# loom_motordriver.net
KiCad netlist of a schematic drawn in EAGLE
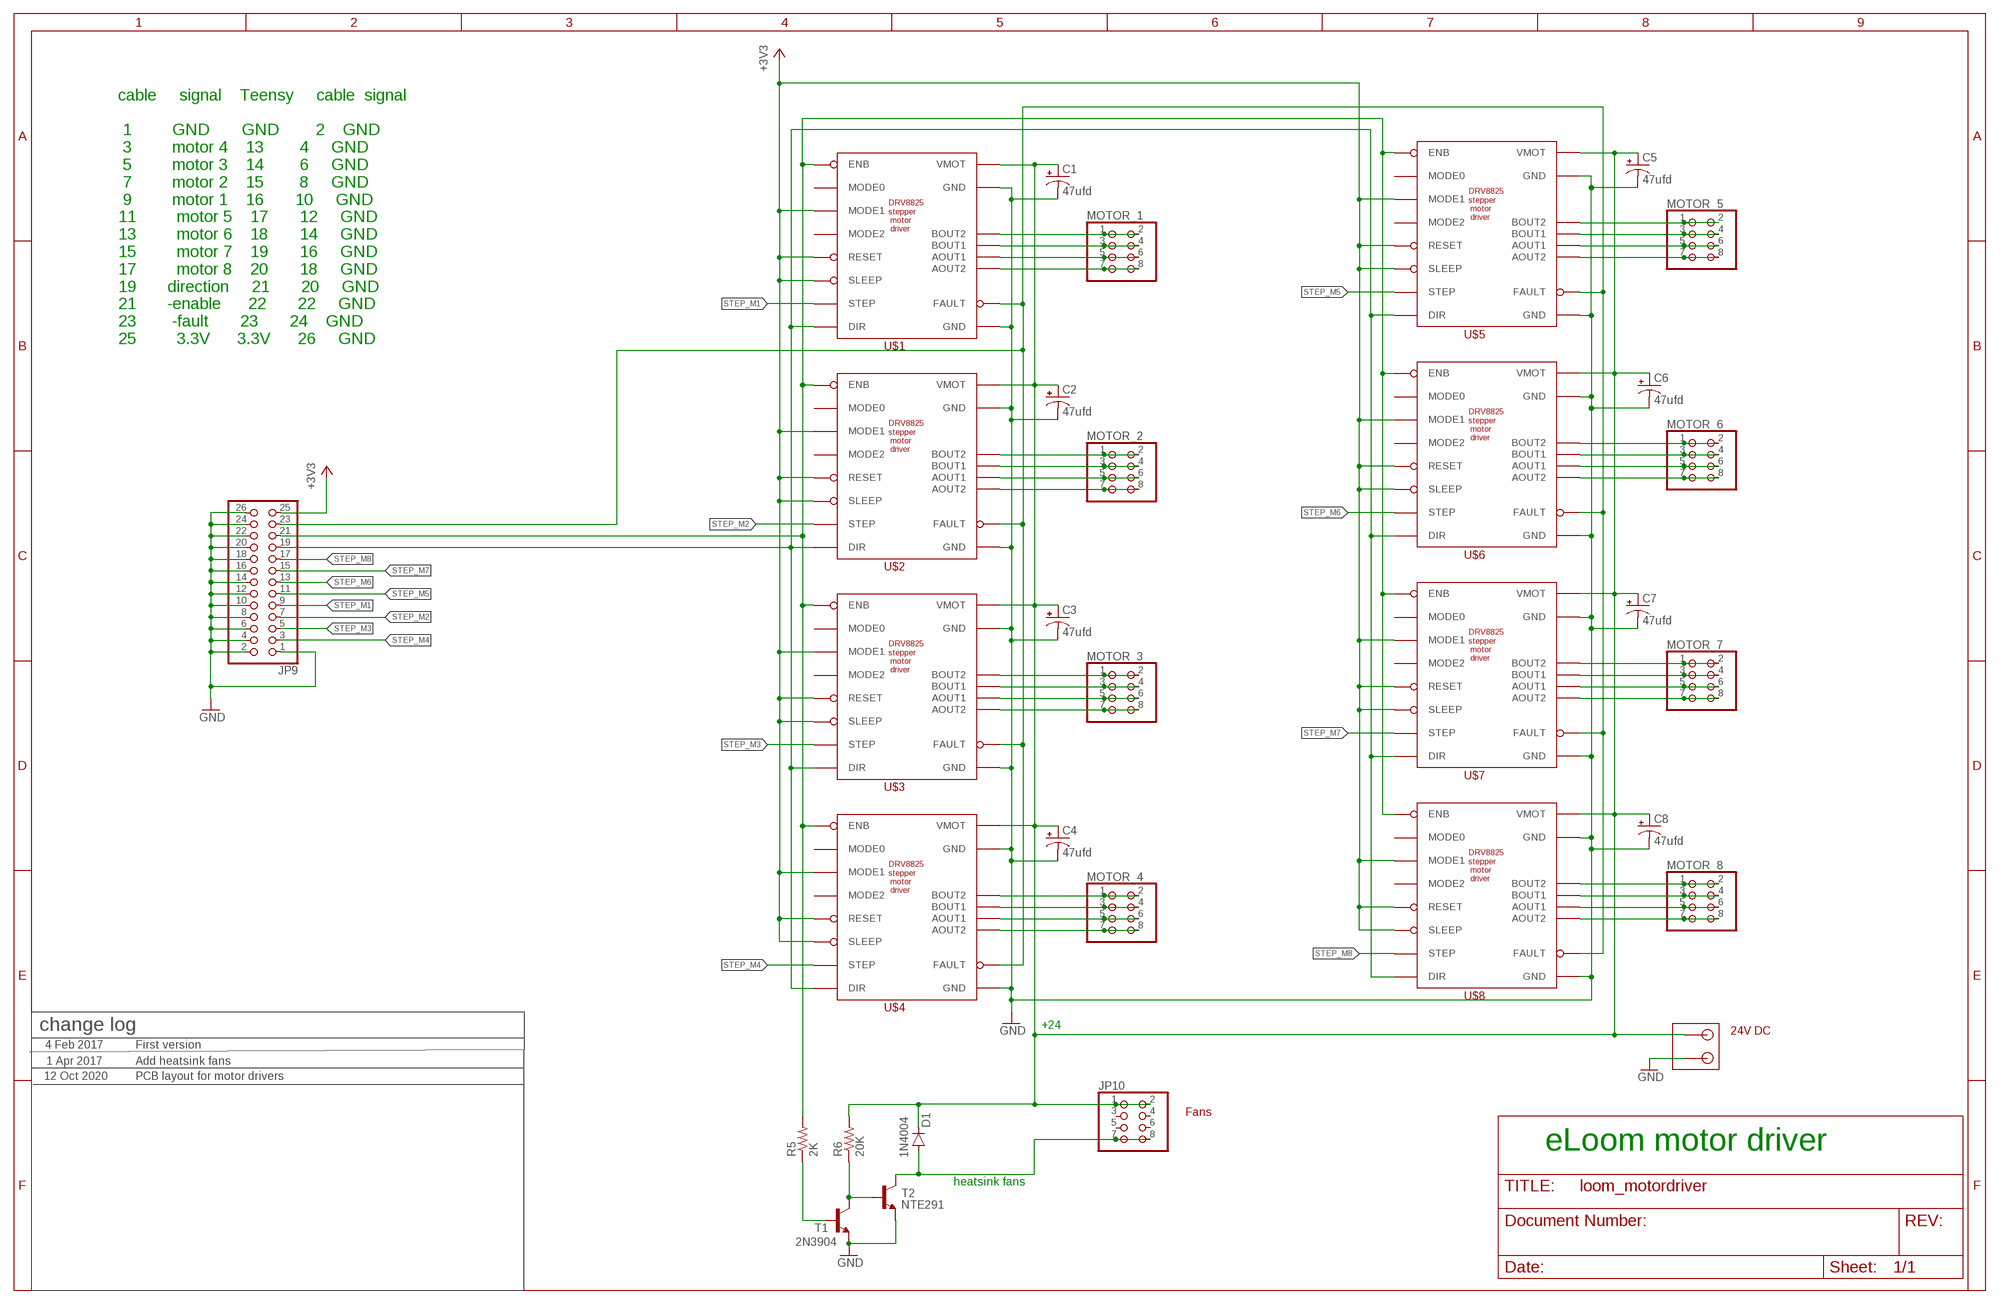
[diagram p0: schematic, sheet 1]

(export (version "E")
  (design (tool "Eeschema 10.0.6"))
  (components
    (comp (ref "C1")
      (value "47ufd")
      (footprint "eagle-import:E2,5-6")
      (libsource (lib "eagle-import") (part "CPOL-USE2.5-6"))
    )
    (comp (ref "C2")
      (value "47ufd")
      (footprint "eagle-import:E2,5-6")
      (libsource (lib "eagle-import") (part "CPOL-USE2.5-6"))
    )
    (comp (ref "C3")
      (value "47ufd")
      (footprint "eagle-import:E2,5-6")
      (libsource (lib "eagle-import") (part "CPOL-USE2.5-6"))
    )
    (comp (ref "C4")
      (value "47ufd")
      (footprint "eagle-import:E2,5-6")
      (libsource (lib "eagle-import") (part "CPOL-USE2.5-6"))
    )
    (comp (ref "C5")
      (value "47ufd")
      (footprint "eagle-import:E2,5-6")
      (libsource (lib "eagle-import") (part "CPOL-USE2.5-6"))
    )
    (comp (ref "C6")
      (value "47ufd")
      (footprint "eagle-import:E2,5-6")
      (libsource (lib "eagle-import") (part "CPOL-USE2.5-6"))
    )
    (comp (ref "C7")
      (value "47ufd")
      (footprint "eagle-import:E2,5-6")
      (libsource (lib "eagle-import") (part "CPOL-USE2.5-6"))
    )
    (comp (ref "C8")
      (value "47ufd")
      (footprint "eagle-import:E2,5-6")
      (libsource (lib "eagle-import") (part "CPOL-USE2.5-6"))
    )
    (comp (ref "D1")
      (value "1N4004")
      (footprint "eagle-import:DO41-10")
      (libsource (lib "eagle-import") (part "1N4004"))
    )
    (comp (ref "JP9")
      (value "PINHD-2X13")
      (footprint "eagle-import:2X13")
      (libsource (lib "eagle-import") (part "PINHD-2X13"))
    )
    (comp (ref "JP10")
      (value "PINHD-2X4")
      (footprint "eagle-import:2X04")
      (libsource (lib "eagle-import") (part "pinhead_325_PINHD-2X4"))
    )
    (comp (ref "MOTOR_1")
      (value "PINHD-2X4")
      (footprint "eagle-import:2X04")
      (libsource (lib "eagle-import") (part "PINHD-2X4"))
    )
    (comp (ref "MOTOR_2")
      (value "PINHD-2X4")
      (footprint "eagle-import:2X04")
      (libsource (lib "eagle-import") (part "PINHD-2X4"))
    )
    (comp (ref "MOTOR_3")
      (value "PINHD-2X4")
      (footprint "eagle-import:2X04")
      (libsource (lib "eagle-import") (part "PINHD-2X4"))
    )
    (comp (ref "MOTOR_4")
      (value "PINHD-2X4")
      (footprint "eagle-import:2X04")
      (libsource (lib "eagle-import") (part "PINHD-2X4"))
    )
    (comp (ref "MOTOR_5")
      (value "PINHD-2X4")
      (footprint "eagle-import:2X04")
      (libsource (lib "eagle-import") (part "PINHD-2X4"))
    )
    (comp (ref "MOTOR_6")
      (value "PINHD-2X4")
      (footprint "eagle-import:2X04")
      (libsource (lib "eagle-import") (part "PINHD-2X4"))
    )
    (comp (ref "MOTOR_7")
      (value "PINHD-2X4")
      (footprint "eagle-import:2X04")
      (libsource (lib "eagle-import") (part "PINHD-2X4"))
    )
    (comp (ref "MOTOR_8")
      (value "PINHD-2X4")
      (footprint "eagle-import:2X04")
      (libsource (lib "eagle-import") (part "PINHD-2X4"))
    )
    (comp (ref "R5")
      (value "2K")
      (footprint "eagle-import:0204_7")
      (libsource (lib "eagle-import") (part "R-US_0204/7"))
    )
    (comp (ref "R6")
      (value "20K")
      (footprint "eagle-import:0204_7")
      (libsource (lib "eagle-import") (part "R-US_0204/7"))
    )
    (comp (ref "T1")
      (value "2N3904")
      (footprint "eagle-import:TO92")
      (libsource (lib "eagle-import") (part "2N3904"))
    )
    (comp (ref "T2")
      (value "NTE291")
      (footprint "eagle-import:TO220")
      (libsource (lib "eagle-import") (part "-NPN-TO220"))
    )
    (comp (ref "U$1")
      (value "DRV8825_STEPPER_MOTOR_DRIVER")
      (footprint "eagle-import:DRV8825_STEPPER_MOTOR_DRIVER")
      (libsource (lib "eagle-import") (part "DRV8825_STEPPER_MOTOR_DRIVER"))
    )
    (comp (ref "U$2")
      (value "DRV8825_STEPPER_MOTOR_DRIVER")
      (footprint "eagle-import:DRV8825_STEPPER_MOTOR_DRIVER")
      (libsource (lib "eagle-import") (part "DRV8825_STEPPER_MOTOR_DRIVER"))
    )
    (comp (ref "U$3")
      (value "DRV8825_STEPPER_MOTOR_DRIVER")
      (footprint "eagle-import:DRV8825_STEPPER_MOTOR_DRIVER")
      (libsource (lib "eagle-import") (part "DRV8825_STEPPER_MOTOR_DRIVER"))
    )
    (comp (ref "U$4")
      (value "DRV8825_STEPPER_MOTOR_DRIVER")
      (footprint "eagle-import:DRV8825_STEPPER_MOTOR_DRIVER")
      (libsource (lib "eagle-import") (part "DRV8825_STEPPER_MOTOR_DRIVER"))
    )
    (comp (ref "U$5")
      (value "DRV8825_STEPPER_MOTOR_DRIVER")
      (footprint "eagle-import:DRV8825_STEPPER_MOTOR_DRIVER")
      (libsource (lib "eagle-import") (part "DRV8825_STEPPER_MOTOR_DRIVER"))
    )
    (comp (ref "U$6")
      (value "DRV8825_STEPPER_MOTOR_DRIVER")
      (footprint "eagle-import:DRV8825_STEPPER_MOTOR_DRIVER")
      (libsource (lib "eagle-import") (part "DRV8825_STEPPER_MOTOR_DRIVER"))
    )
    (comp (ref "U$7")
      (value "DRV8825_STEPPER_MOTOR_DRIVER")
      (footprint "eagle-import:DRV8825_STEPPER_MOTOR_DRIVER")
      (libsource (lib "eagle-import") (part "DRV8825_STEPPER_MOTOR_DRIVER"))
    )
    (comp (ref "U$8")
      (value "DRV8825_STEPPER_MOTOR_DRIVER")
      (footprint "eagle-import:DRV8825_STEPPER_MOTOR_DRIVER")
      (libsource (lib "eagle-import") (part "DRV8825_STEPPER_MOTOR_DRIVER"))
    )
    (comp (ref "U$9")
      (value "CONNECTOR-2PIN")
      (footprint "eagle-import:CONNECTOR-2PIN-5MM")
      (libsource (lib "eagle-import") (part "CONNECTOR-2PIN"))
    )
  )
  (nets
    (net (code "1") (name "+3V3") (class "Default")
      (node (ref "JP9") (pin "25") (pinfunction "25_25") (pintype "passive"))
      (node (ref "U$1") (pin "P$3") (pinfunction "MODE1_P$3") (pintype "input"))
      (node (ref "U$1") (pin "P$5") (pinfunction "RESET_P$5") (pintype "input"))
      (node (ref "U$1") (pin "P$6") (pinfunction "SLEEP_P$6") (pintype "input"))
      (node (ref "U$2") (pin "P$3") (pinfunction "MODE1_P$3") (pintype "input"))
      (node (ref "U$2") (pin "P$5") (pinfunction "RESET_P$5") (pintype "input"))
      (node (ref "U$2") (pin "P$6") (pinfunction "SLEEP_P$6") (pintype "input"))
      (node (ref "U$3") (pin "P$3") (pinfunction "MODE1_P$3") (pintype "input"))
      (node (ref "U$3") (pin "P$5") (pinfunction "RESET_P$5") (pintype "input"))
      (node (ref "U$3") (pin "P$6") (pinfunction "SLEEP_P$6") (pintype "input"))
      (node (ref "U$4") (pin "P$3") (pinfunction "MODE1_P$3") (pintype "input"))
      (node (ref "U$4") (pin "P$5") (pinfunction "RESET_P$5") (pintype "input"))
      (node (ref "U$4") (pin "P$6") (pinfunction "SLEEP_P$6") (pintype "input"))
      (node (ref "U$5") (pin "P$3") (pinfunction "MODE1_P$3") (pintype "input"))
      (node (ref "U$5") (pin "P$5") (pinfunction "RESET_P$5") (pintype "input"))
      (node (ref "U$5") (pin "P$6") (pinfunction "SLEEP_P$6") (pintype "input"))
      (node (ref "U$6") (pin "P$3") (pinfunction "MODE1_P$3") (pintype "input"))
      (node (ref "U$6") (pin "P$5") (pinfunction "RESET_P$5") (pintype "input"))
      (node (ref "U$6") (pin "P$6") (pinfunction "SLEEP_P$6") (pintype "input"))
      (node (ref "U$7") (pin "P$3") (pinfunction "MODE1_P$3") (pintype "input"))
      (node (ref "U$7") (pin "P$5") (pinfunction "RESET_P$5") (pintype "input"))
      (node (ref "U$7") (pin "P$6") (pinfunction "SLEEP_P$6") (pintype "input"))
      (node (ref "U$8") (pin "P$3") (pinfunction "MODE1_P$3") (pintype "input"))
      (node (ref "U$8") (pin "P$5") (pinfunction "RESET_P$5") (pintype "input"))
      (node (ref "U$8") (pin "P$6") (pinfunction "SLEEP_P$6") (pintype "input"))
    )
    (net (code "2") (name "GND") (class "Default")
      (node (ref "C1") (pin "-") (pinfunction "-_-") (pintype "passive"))
      (node (ref "C2") (pin "-") (pinfunction "-_-") (pintype "passive"))
      (node (ref "C3") (pin "-") (pinfunction "-_-") (pintype "passive"))
      (node (ref "C4") (pin "-") (pinfunction "-_-") (pintype "passive"))
      (node (ref "C5") (pin "-") (pinfunction "-_-") (pintype "passive"))
      (node (ref "C6") (pin "-") (pinfunction "-_-") (pintype "passive"))
      (node (ref "C7") (pin "-") (pinfunction "-_-") (pintype "passive"))
      (node (ref "C8") (pin "-") (pinfunction "-_-") (pintype "passive"))
      (node (ref "JP9") (pin "1") (pinfunction "1_1") (pintype "passive"))
      (node (ref "JP9") (pin "10") (pinfunction "10_10") (pintype "passive"))
      (node (ref "JP9") (pin "12") (pinfunction "12_12") (pintype "passive"))
      (node (ref "JP9") (pin "14") (pinfunction "14_14") (pintype "passive"))
      (node (ref "JP9") (pin "16") (pinfunction "16_16") (pintype "passive"))
      (node (ref "JP9") (pin "18") (pinfunction "18_18") (pintype "passive"))
      (node (ref "JP9") (pin "2") (pinfunction "2_2") (pintype "passive"))
      (node (ref "JP9") (pin "20") (pinfunction "20_20") (pintype "passive"))
      (node (ref "JP9") (pin "22") (pinfunction "22_22") (pintype "passive"))
      (node (ref "JP9") (pin "24") (pinfunction "24_24") (pintype "passive"))
      (node (ref "JP9") (pin "26") (pinfunction "26_26") (pintype "passive"))
      (node (ref "JP9") (pin "4") (pinfunction "4_4") (pintype "passive"))
      (node (ref "JP9") (pin "6") (pinfunction "6_6") (pintype "passive"))
      (node (ref "JP9") (pin "8") (pinfunction "8_8") (pintype "passive"))
      (node (ref "T1") (pin "3") (pinfunction "E_3") (pintype "passive"))
      (node (ref "T2") (pin "3") (pinfunction "E_3") (pintype "passive"))
      (node (ref "U$1") (pin "P$15") (pinfunction "GND_P$15") (pintype "power_in"))
      (node (ref "U$1") (pin "P$9") (pinfunction "GND_P$9") (pintype "power_in"))
      (node (ref "U$2") (pin "P$15") (pinfunction "GND_P$15") (pintype "power_in"))
      (node (ref "U$2") (pin "P$9") (pinfunction "GND_P$9") (pintype "power_in"))
      (node (ref "U$3") (pin "P$15") (pinfunction "GND_P$15") (pintype "power_in"))
      (node (ref "U$3") (pin "P$9") (pinfunction "GND_P$9") (pintype "power_in"))
      (node (ref "U$4") (pin "P$15") (pinfunction "GND_P$15") (pintype "power_in"))
      (node (ref "U$4") (pin "P$9") (pinfunction "GND_P$9") (pintype "power_in"))
      (node (ref "U$5") (pin "P$15") (pinfunction "GND_P$15") (pintype "power_in"))
      (node (ref "U$5") (pin "P$9") (pinfunction "GND_P$9") (pintype "power_in"))
      (node (ref "U$6") (pin "P$15") (pinfunction "GND_P$15") (pintype "power_in"))
      (node (ref "U$6") (pin "P$9") (pinfunction "GND_P$9") (pintype "power_in"))
      (node (ref "U$7") (pin "P$15") (pinfunction "GND_P$15") (pintype "power_in"))
      (node (ref "U$7") (pin "P$9") (pinfunction "GND_P$9") (pintype "power_in"))
      (node (ref "U$8") (pin "P$15") (pinfunction "GND_P$15") (pintype "power_in"))
      (node (ref "U$8") (pin "P$9") (pinfunction "GND_P$9") (pintype "power_in"))
      (node (ref "U$9") (pin "P$2") (pinfunction "P$2_P$2") (pintype "bidirectional"))
    )
    (net (code "3") (name "Net-(T1-B)") (class "Default")
      (node (ref "R5") (pin "1") (pinfunction "1_1") (pintype "passive"))
      (node (ref "T1") (pin "2") (pinfunction "B_2") (pintype "passive"))
    )
    (net (code "4") (name "Net-(T1-C)") (class "Default")
      (node (ref "R6") (pin "1") (pinfunction "1_1") (pintype "passive"))
      (node (ref "T1") (pin "1") (pinfunction "C_1") (pintype "passive"))
      (node (ref "T2") (pin "1") (pinfunction "B_1") (pintype "passive"))
    )
    (net (code "5") (name "Net-(T2-C)") (class "Default")
      (node (ref "D1") (pin "A") (pinfunction "A_A") (pintype "passive"))
      (node (ref "JP10") (pin "7") (pinfunction "7_7") (pintype "passive"))
      (node (ref "JP10") (pin "8") (pinfunction "8_8") (pintype "passive"))
      (node (ref "T2") (pin "2") (pinfunction "C_2") (pintype "passive"))
    )
    (net (code "6") (name "Net-(U$1-AOUT1)") (class "Default")
      (node (ref "MOTOR_1") (pin "5") (pinfunction "5_5") (pintype "passive"))
      (node (ref "MOTOR_1") (pin "6") (pinfunction "6_6") (pintype "passive"))
      (node (ref "U$1") (pin "P$12") (pinfunction "AOUT1_P$12") (pintype "passive"))
    )
    (net (code "7") (name "Net-(U$1-AOUT2)") (class "Default")
      (node (ref "MOTOR_1") (pin "7") (pinfunction "7_7") (pintype "passive"))
      (node (ref "MOTOR_1") (pin "8") (pinfunction "8_8") (pintype "passive"))
      (node (ref "U$1") (pin "P$11") (pinfunction "AOUT2_P$11") (pintype "passive"))
    )
    (net (code "8") (name "Net-(U$1-BOUT1)") (class "Default")
      (node (ref "MOTOR_1") (pin "3") (pinfunction "3_3") (pintype "passive"))
      (node (ref "MOTOR_1") (pin "4") (pinfunction "4_4") (pintype "passive"))
      (node (ref "U$1") (pin "P$13") (pinfunction "BOUT1_P$13") (pintype "passive"))
    )
    (net (code "9") (name "Net-(U$1-BOUT2)") (class "Default")
      (node (ref "MOTOR_1") (pin "1") (pinfunction "1_1") (pintype "passive"))
      (node (ref "MOTOR_1") (pin "2") (pinfunction "2_2") (pintype "passive"))
      (node (ref "U$1") (pin "P$14") (pinfunction "BOUT2_P$14") (pintype "passive"))
    )
    (net (code "10") (name "Net-(U$1-DIR)") (class "Default")
      (node (ref "JP9") (pin "19") (pinfunction "19_19") (pintype "passive"))
      (node (ref "U$1") (pin "P$8") (pinfunction "DIR_P$8") (pintype "input"))
      (node (ref "U$2") (pin "P$8") (pinfunction "DIR_P$8") (pintype "input"))
      (node (ref "U$3") (pin "P$8") (pinfunction "DIR_P$8") (pintype "input"))
      (node (ref "U$4") (pin "P$8") (pinfunction "DIR_P$8") (pintype "input"))
      (node (ref "U$5") (pin "P$8") (pinfunction "DIR_P$8") (pintype "input"))
      (node (ref "U$6") (pin "P$8") (pinfunction "DIR_P$8") (pintype "input"))
      (node (ref "U$7") (pin "P$8") (pinfunction "DIR_P$8") (pintype "input"))
      (node (ref "U$8") (pin "P$8") (pinfunction "DIR_P$8") (pintype "input"))
    )
    (net (code "11") (name "Net-(U$1-ENB)") (class "Default")
      (node (ref "JP9") (pin "21") (pinfunction "21_21") (pintype "passive"))
      (node (ref "R5") (pin "2") (pinfunction "2_2") (pintype "passive"))
      (node (ref "U$1") (pin "P$1") (pinfunction "ENB_P$1") (pintype "input"))
      (node (ref "U$2") (pin "P$1") (pinfunction "ENB_P$1") (pintype "input"))
      (node (ref "U$3") (pin "P$1") (pinfunction "ENB_P$1") (pintype "input"))
      (node (ref "U$4") (pin "P$1") (pinfunction "ENB_P$1") (pintype "input"))
      (node (ref "U$5") (pin "P$1") (pinfunction "ENB_P$1") (pintype "input"))
      (node (ref "U$6") (pin "P$1") (pinfunction "ENB_P$1") (pintype "input"))
      (node (ref "U$7") (pin "P$1") (pinfunction "ENB_P$1") (pintype "input"))
      (node (ref "U$8") (pin "P$1") (pinfunction "ENB_P$1") (pintype "input"))
    )
    (net (code "12") (name "Net-(U$1-FAULT)") (class "Default")
      (node (ref "JP9") (pin "23") (pinfunction "23_23") (pintype "passive"))
      (node (ref "U$1") (pin "P$10") (pinfunction "FAULT_P$10") (pintype "output"))
      (node (ref "U$2") (pin "P$10") (pinfunction "FAULT_P$10") (pintype "output"))
      (node (ref "U$3") (pin "P$10") (pinfunction "FAULT_P$10") (pintype "output"))
      (node (ref "U$4") (pin "P$10") (pinfunction "FAULT_P$10") (pintype "output"))
      (node (ref "U$5") (pin "P$10") (pinfunction "FAULT_P$10") (pintype "output"))
      (node (ref "U$6") (pin "P$10") (pinfunction "FAULT_P$10") (pintype "output"))
      (node (ref "U$7") (pin "P$10") (pinfunction "FAULT_P$10") (pintype "output"))
      (node (ref "U$8") (pin "P$10") (pinfunction "FAULT_P$10") (pintype "output"))
    )
    (net (code "13") (name "Net-(U$1-VMOT)") (class "Default")
      (node (ref "C1") (pin "+") (pinfunction "+_+") (pintype "passive"))
      (node (ref "C2") (pin "+") (pinfunction "+_+") (pintype "passive"))
      (node (ref "C3") (pin "+") (pinfunction "+_+") (pintype "passive"))
      (node (ref "C4") (pin "+") (pinfunction "+_+") (pintype "passive"))
      (node (ref "C5") (pin "+") (pinfunction "+_+") (pintype "passive"))
      (node (ref "C6") (pin "+") (pinfunction "+_+") (pintype "passive"))
      (node (ref "C7") (pin "+") (pinfunction "+_+") (pintype "passive"))
      (node (ref "C8") (pin "+") (pinfunction "+_+") (pintype "passive"))
      (node (ref "D1") (pin "C") (pinfunction "C_C") (pintype "passive"))
      (node (ref "JP10") (pin "1") (pinfunction "1_1") (pintype "passive"))
      (node (ref "JP10") (pin "2") (pinfunction "2_2") (pintype "passive"))
      (node (ref "R6") (pin "2") (pinfunction "2_2") (pintype "passive"))
      (node (ref "U$1") (pin "P$16") (pinfunction "VMOT_P$16") (pintype "power_in"))
      (node (ref "U$2") (pin "P$16") (pinfunction "VMOT_P$16") (pintype "power_in"))
      (node (ref "U$3") (pin "P$16") (pinfunction "VMOT_P$16") (pintype "power_in"))
      (node (ref "U$4") (pin "P$16") (pinfunction "VMOT_P$16") (pintype "power_in"))
      (node (ref "U$5") (pin "P$16") (pinfunction "VMOT_P$16") (pintype "power_in"))
      (node (ref "U$6") (pin "P$16") (pinfunction "VMOT_P$16") (pintype "power_in"))
      (node (ref "U$7") (pin "P$16") (pinfunction "VMOT_P$16") (pintype "power_in"))
      (node (ref "U$8") (pin "P$16") (pinfunction "VMOT_P$16") (pintype "power_in"))
      (node (ref "U$9") (pin "P$1") (pinfunction "P$1_P$1") (pintype "bidirectional"))
    )
    (net (code "14") (name "Net-(U$2-AOUT1)") (class "Default")
      (node (ref "MOTOR_2") (pin "5") (pinfunction "5_5") (pintype "passive"))
      (node (ref "MOTOR_2") (pin "6") (pinfunction "6_6") (pintype "passive"))
      (node (ref "U$2") (pin "P$12") (pinfunction "AOUT1_P$12") (pintype "passive"))
    )
    (net (code "15") (name "Net-(U$2-AOUT2)") (class "Default")
      (node (ref "MOTOR_2") (pin "7") (pinfunction "7_7") (pintype "passive"))
      (node (ref "MOTOR_2") (pin "8") (pinfunction "8_8") (pintype "passive"))
      (node (ref "U$2") (pin "P$11") (pinfunction "AOUT2_P$11") (pintype "passive"))
    )
    (net (code "16") (name "Net-(U$2-BOUT1)") (class "Default")
      (node (ref "MOTOR_2") (pin "3") (pinfunction "3_3") (pintype "passive"))
      (node (ref "MOTOR_2") (pin "4") (pinfunction "4_4") (pintype "passive"))
      (node (ref "U$2") (pin "P$13") (pinfunction "BOUT1_P$13") (pintype "passive"))
    )
    (net (code "17") (name "Net-(U$2-BOUT2)") (class "Default")
      (node (ref "MOTOR_2") (pin "1") (pinfunction "1_1") (pintype "passive"))
      (node (ref "MOTOR_2") (pin "2") (pinfunction "2_2") (pintype "passive"))
      (node (ref "U$2") (pin "P$14") (pinfunction "BOUT2_P$14") (pintype "passive"))
    )
    (net (code "18") (name "Net-(U$3-AOUT1)") (class "Default")
      (node (ref "MOTOR_3") (pin "5") (pinfunction "5_5") (pintype "passive"))
      (node (ref "MOTOR_3") (pin "6") (pinfunction "6_6") (pintype "passive"))
      (node (ref "U$3") (pin "P$12") (pinfunction "AOUT1_P$12") (pintype "passive"))
    )
    (net (code "19") (name "Net-(U$3-AOUT2)") (class "Default")
      (node (ref "MOTOR_3") (pin "7") (pinfunction "7_7") (pintype "passive"))
      (node (ref "MOTOR_3") (pin "8") (pinfunction "8_8") (pintype "passive"))
      (node (ref "U$3") (pin "P$11") (pinfunction "AOUT2_P$11") (pintype "passive"))
    )
    (net (code "20") (name "Net-(U$3-BOUT1)") (class "Default")
      (node (ref "MOTOR_3") (pin "3") (pinfunction "3_3") (pintype "passive"))
      (node (ref "MOTOR_3") (pin "4") (pinfunction "4_4") (pintype "passive"))
      (node (ref "U$3") (pin "P$13") (pinfunction "BOUT1_P$13") (pintype "passive"))
    )
    (net (code "21") (name "Net-(U$3-BOUT2)") (class "Default")
      (node (ref "MOTOR_3") (pin "1") (pinfunction "1_1") (pintype "passive"))
      (node (ref "MOTOR_3") (pin "2") (pinfunction "2_2") (pintype "passive"))
      (node (ref "U$3") (pin "P$14") (pinfunction "BOUT2_P$14") (pintype "passive"))
    )
    (net (code "22") (name "Net-(U$4-AOUT1)") (class "Default")
      (node (ref "MOTOR_4") (pin "5") (pinfunction "5_5") (pintype "passive"))
      (node (ref "MOTOR_4") (pin "6") (pinfunction "6_6") (pintype "passive"))
      (node (ref "U$4") (pin "P$12") (pinfunction "AOUT1_P$12") (pintype "passive"))
    )
    (net (code "23") (name "Net-(U$4-AOUT2)") (class "Default")
      (node (ref "MOTOR_4") (pin "7") (pinfunction "7_7") (pintype "passive"))
      (node (ref "MOTOR_4") (pin "8") (pinfunction "8_8") (pintype "passive"))
      (node (ref "U$4") (pin "P$11") (pinfunction "AOUT2_P$11") (pintype "passive"))
    )
    (net (code "24") (name "Net-(U$4-BOUT1)") (class "Default")
      (node (ref "MOTOR_4") (pin "3") (pinfunction "3_3") (pintype "passive"))
      (node (ref "MOTOR_4") (pin "4") (pinfunction "4_4") (pintype "passive"))
      (node (ref "U$4") (pin "P$13") (pinfunction "BOUT1_P$13") (pintype "passive"))
    )
    (net (code "25") (name "Net-(U$4-BOUT2)") (class "Default")
      (node (ref "MOTOR_4") (pin "1") (pinfunction "1_1") (pintype "passive"))
      (node (ref "MOTOR_4") (pin "2") (pinfunction "2_2") (pintype "passive"))
      (node (ref "U$4") (pin "P$14") (pinfunction "BOUT2_P$14") (pintype "passive"))
    )
    (net (code "26") (name "Net-(U$5-AOUT1)") (class "Default")
      (node (ref "MOTOR_5") (pin "5") (pinfunction "5_5") (pintype "passive"))
      (node (ref "MOTOR_5") (pin "6") (pinfunction "6_6") (pintype "passive"))
      (node (ref "U$5") (pin "P$12") (pinfunction "AOUT1_P$12") (pintype "passive"))
    )
    (net (code "27") (name "Net-(U$5-AOUT2)") (class "Default")
      (node (ref "MOTOR_5") (pin "7") (pinfunction "7_7") (pintype "passive"))
      (node (ref "MOTOR_5") (pin "8") (pinfunction "8_8") (pintype "passive"))
      (node (ref "U$5") (pin "P$11") (pinfunction "AOUT2_P$11") (pintype "passive"))
    )
    (net (code "28") (name "Net-(U$5-BOUT1)") (class "Default")
      (node (ref "MOTOR_5") (pin "3") (pinfunction "3_3") (pintype "passive"))
      (node (ref "MOTOR_5") (pin "4") (pinfunction "4_4") (pintype "passive"))
      (node (ref "U$5") (pin "P$13") (pinfunction "BOUT1_P$13") (pintype "passive"))
    )
    (net (code "29") (name "Net-(U$5-BOUT2)") (class "Default")
      (node (ref "MOTOR_5") (pin "1") (pinfunction "1_1") (pintype "passive"))
      (node (ref "MOTOR_5") (pin "2") (pinfunction "2_2") (pintype "passive"))
      (node (ref "U$5") (pin "P$14") (pinfunction "BOUT2_P$14") (pintype "passive"))
    )
    (net (code "30") (name "Net-(U$6-AOUT1)") (class "Default")
      (node (ref "MOTOR_6") (pin "5") (pinfunction "5_5") (pintype "passive"))
      (node (ref "MOTOR_6") (pin "6") (pinfunction "6_6") (pintype "passive"))
      (node (ref "U$6") (pin "P$12") (pinfunction "AOUT1_P$12") (pintype "passive"))
    )
    (net (code "31") (name "Net-(U$6-AOUT2)") (class "Default")
      (node (ref "MOTOR_6") (pin "7") (pinfunction "7_7") (pintype "passive"))
      (node (ref "MOTOR_6") (pin "8") (pinfunction "8_8") (pintype "passive"))
      (node (ref "U$6") (pin "P$11") (pinfunction "AOUT2_P$11") (pintype "passive"))
    )
    (net (code "32") (name "Net-(U$6-BOUT1)") (class "Default")
      (node (ref "MOTOR_6") (pin "3") (pinfunction "3_3") (pintype "passive"))
      (node (ref "MOTOR_6") (pin "4") (pinfunction "4_4") (pintype "passive"))
      (node (ref "U$6") (pin "P$13") (pinfunction "BOUT1_P$13") (pintype "passive"))
    )
    (net (code "33") (name "Net-(U$6-BOUT2)") (class "Default")
      (node (ref "MOTOR_6") (pin "1") (pinfunction "1_1") (pintype "passive"))
      (node (ref "MOTOR_6") (pin "2") (pinfunction "2_2") (pintype "passive"))
      (node (ref "U$6") (pin "P$14") (pinfunction "BOUT2_P$14") (pintype "passive"))
    )
    (net (code "34") (name "Net-(U$7-AOUT1)") (class "Default")
      (node (ref "MOTOR_7") (pin "5") (pinfunction "5_5") (pintype "passive"))
      (node (ref "MOTOR_7") (pin "6") (pinfunction "6_6") (pintype "passive"))
      (node (ref "U$7") (pin "P$12") (pinfunction "AOUT1_P$12") (pintype "passive"))
    )
    (net (code "35") (name "Net-(U$7-AOUT2)") (class "Default")
      (node (ref "MOTOR_7") (pin "7") (pinfunction "7_7") (pintype "passive"))
      (node (ref "MOTOR_7") (pin "8") (pinfunction "8_8") (pintype "passive"))
      (node (ref "U$7") (pin "P$11") (pinfunction "AOUT2_P$11") (pintype "passive"))
    )
    (net (code "36") (name "Net-(U$7-BOUT1)") (class "Default")
      (node (ref "MOTOR_7") (pin "3") (pinfunction "3_3") (pintype "passive"))
      (node (ref "MOTOR_7") (pin "4") (pinfunction "4_4") (pintype "passive"))
      (node (ref "U$7") (pin "P$13") (pinfunction "BOUT1_P$13") (pintype "passive"))
    )
    (net (code "37") (name "Net-(U$7-BOUT2)") (class "Default")
      (node (ref "MOTOR_7") (pin "1") (pinfunction "1_1") (pintype "passive"))
      (node (ref "MOTOR_7") (pin "2") (pinfunction "2_2") (pintype "passive"))
      (node (ref "U$7") (pin "P$14") (pinfunction "BOUT2_P$14") (pintype "passive"))
    )
    (net (code "38") (name "Net-(U$8-AOUT1)") (class "Default")
      (node (ref "MOTOR_8") (pin "5") (pinfunction "5_5") (pintype "passive"))
      (node (ref "MOTOR_8") (pin "6") (pinfunction "6_6") (pintype "passive"))
      (node (ref "U$8") (pin "P$12") (pinfunction "AOUT1_P$12") (pintype "passive"))
    )
    (net (code "39") (name "Net-(U$8-AOUT2)") (class "Default")
      (node (ref "MOTOR_8") (pin "7") (pinfunction "7_7") (pintype "passive"))
      (node (ref "MOTOR_8") (pin "8") (pinfunction "8_8") (pintype "passive"))
      (node (ref "U$8") (pin "P$11") (pinfunction "AOUT2_P$11") (pintype "passive"))
    )
    (net (code "40") (name "Net-(U$8-BOUT1)") (class "Default")
      (node (ref "MOTOR_8") (pin "3") (pinfunction "3_3") (pintype "passive"))
      (node (ref "MOTOR_8") (pin "4") (pinfunction "4_4") (pintype "passive"))
      (node (ref "U$8") (pin "P$13") (pinfunction "BOUT1_P$13") (pintype "passive"))
    )
    (net (code "41") (name "Net-(U$8-BOUT2)") (class "Default")
      (node (ref "MOTOR_8") (pin "1") (pinfunction "1_1") (pintype "passive"))
      (node (ref "MOTOR_8") (pin "2") (pinfunction "2_2") (pintype "passive"))
      (node (ref "U$8") (pin "P$14") (pinfunction "BOUT2_P$14") (pintype "passive"))
    )
    (net (code "42") (name "STEP_M1") (class "Default")
      (node (ref "JP9") (pin "9") (pinfunction "9_9") (pintype "passive"))
      (node (ref "U$1") (pin "P$7") (pinfunction "STEP_P$7") (pintype "input"))
    )
    (net (code "43") (name "STEP_M2") (class "Default")
      (node (ref "JP9") (pin "7") (pinfunction "7_7") (pintype "passive"))
      (node (ref "U$2") (pin "P$7") (pinfunction "STEP_P$7") (pintype "input"))
    )
    (net (code "44") (name "STEP_M3") (class "Default")
      (node (ref "JP9") (pin "5") (pinfunction "5_5") (pintype "passive"))
      (node (ref "U$3") (pin "P$7") (pinfunction "STEP_P$7") (pintype "input"))
    )
    (net (code "45") (name "STEP_M4") (class "Default")
      (node (ref "JP9") (pin "3") (pinfunction "3_3") (pintype "passive"))
      (node (ref "U$4") (pin "P$7") (pinfunction "STEP_P$7") (pintype "input"))
    )
    (net (code "46") (name "STEP_M5") (class "Default")
      (node (ref "JP9") (pin "11") (pinfunction "11_11") (pintype "passive"))
      (node (ref "U$5") (pin "P$7") (pinfunction "STEP_P$7") (pintype "input"))
    )
    (net (code "47") (name "STEP_M6") (class "Default")
      (node (ref "JP9") (pin "13") (pinfunction "13_13") (pintype "passive"))
      (node (ref "U$6") (pin "P$7") (pinfunction "STEP_P$7") (pintype "input"))
    )
    (net (code "48") (name "STEP_M7") (class "Default")
      (node (ref "JP9") (pin "15") (pinfunction "15_15") (pintype "passive"))
      (node (ref "U$7") (pin "P$7") (pinfunction "STEP_P$7") (pintype "input"))
    )
    (net (code "49") (name "STEP_M8") (class "Default")
      (node (ref "JP9") (pin "17") (pinfunction "17_17") (pintype "passive"))
      (node (ref "U$8") (pin "P$7") (pinfunction "STEP_P$7") (pintype "input"))
    )
    (net (code "50") (name "unconnected-(JP10-Pad3)") (class "Default")
      (node (ref "JP10") (pin "3") (pinfunction "3_3") (pintype "passive"))
    )
    (net (code "51") (name "unconnected-(JP10-Pad4)") (class "Default")
      (node (ref "JP10") (pin "4") (pinfunction "4_4") (pintype "passive"))
    )
    (net (code "52") (name "unconnected-(JP10-Pad5)") (class "Default")
      (node (ref "JP10") (pin "5") (pinfunction "5_5") (pintype "passive"))
    )
    (net (code "53") (name "unconnected-(JP10-Pad6)") (class "Default")
      (node (ref "JP10") (pin "6") (pinfunction "6_6") (pintype "passive"))
    )
    (net (code "54") (name "unconnected-(U$1-MODE0-PadP$2)") (class "Default")
      (node (ref "U$1") (pin "P$2") (pinfunction "MODE0_P$2") (pintype "input"))
    )
    (net (code "55") (name "unconnected-(U$1-MODE2-PadP$4)") (class "Default")
      (node (ref "U$1") (pin "P$4") (pinfunction "MODE2_P$4") (pintype "input"))
    )
    (net (code "56") (name "unconnected-(U$2-MODE0-PadP$2)") (class "Default")
      (node (ref "U$2") (pin "P$2") (pinfunction "MODE0_P$2") (pintype "input"))
    )
    (net (code "57") (name "unconnected-(U$2-MODE2-PadP$4)") (class "Default")
      (node (ref "U$2") (pin "P$4") (pinfunction "MODE2_P$4") (pintype "input"))
    )
    (net (code "58") (name "unconnected-(U$3-MODE0-PadP$2)") (class "Default")
      (node (ref "U$3") (pin "P$2") (pinfunction "MODE0_P$2") (pintype "input"))
    )
    (net (code "59") (name "unconnected-(U$3-MODE2-PadP$4)") (class "Default")
      (node (ref "U$3") (pin "P$4") (pinfunction "MODE2_P$4") (pintype "input"))
    )
    (net (code "60") (name "unconnected-(U$4-MODE0-PadP$2)") (class "Default")
      (node (ref "U$4") (pin "P$2") (pinfunction "MODE0_P$2") (pintype "input"))
    )
    (net (code "61") (name "unconnected-(U$4-MODE2-PadP$4)") (class "Default")
      (node (ref "U$4") (pin "P$4") (pinfunction "MODE2_P$4") (pintype "input"))
    )
    (net (code "62") (name "unconnected-(U$5-MODE0-PadP$2)") (class "Default")
      (node (ref "U$5") (pin "P$2") (pinfunction "MODE0_P$2") (pintype "input"))
    )
    (net (code "63") (name "unconnected-(U$5-MODE2-PadP$4)") (class "Default")
      (node (ref "U$5") (pin "P$4") (pinfunction "MODE2_P$4") (pintype "input"))
    )
    (net (code "64") (name "unconnected-(U$6-MODE0-PadP$2)") (class "Default")
      (node (ref "U$6") (pin "P$2") (pinfunction "MODE0_P$2") (pintype "input"))
    )
    (net (code "65") (name "unconnected-(U$6-MODE2-PadP$4)") (class "Default")
      (node (ref "U$6") (pin "P$4") (pinfunction "MODE2_P$4") (pintype "input"))
    )
    (net (code "66") (name "unconnected-(U$7-MODE0-PadP$2)") (class "Default")
      (node (ref "U$7") (pin "P$2") (pinfunction "MODE0_P$2") (pintype "input"))
    )
    (net (code "67") (name "unconnected-(U$7-MODE2-PadP$4)") (class "Default")
      (node (ref "U$7") (pin "P$4") (pinfunction "MODE2_P$4") (pintype "input"))
    )
    (net (code "68") (name "unconnected-(U$8-MODE0-PadP$2)") (class "Default")
      (node (ref "U$8") (pin "P$2") (pinfunction "MODE0_P$2") (pintype "input"))
    )
    (net (code "69") (name "unconnected-(U$8-MODE2-PadP$4)") (class "Default")
      (node (ref "U$8") (pin "P$4") (pinfunction "MODE2_P$4") (pintype "input"))
    )
  )
)
